# LED.net
KiCad netlist of a schematic drawn in Altium Designer
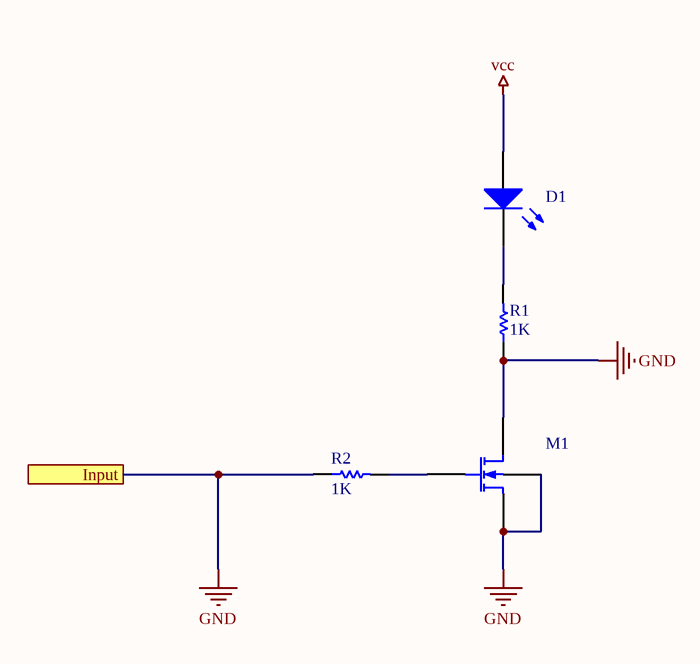
[diagram p0: LED.SchDoc]

(export (version "E")
  (design (tool "Eeschema 10.0.6"))
  (components
    (comp (ref "D1")
      (value "Light-Emitting Diode")
      (libsource (lib "Simulation Generic Components") (part "LED"))
    )
    (comp (ref "M1")
      (value "N-channel MOS1 MOSFET Shichman and Hodges Model")
      (libsource (lib "Simulation Generic Components") (part "MOSFET N-ch Lev1"))
    )
    (comp (ref "R1")
      (value "1K")
      (description "Resistor")
      (libsource (lib "Simulation Generic Components") (part "Resistor"))
    )
    (comp (ref "R2")
      (value "1K")
      (description "Resistor")
      (libsource (lib "Simulation Generic Components") (part "Resistor"))
    )
  )
  (nets
    (net (code "1") (name "GND") (class "Default")
      (node (ref "M1") (pin "1") (pinfunction "D_1") (pintype "passive"))
      (node (ref "M1") (pin "3") (pinfunction "S_3") (pintype "passive"))
      (node (ref "M1") (pin "4") (pinfunction "B_4") (pintype "passive"))
      (node (ref "R1") (pin "1") (pinfunction "1_1") (pintype "passive"))
      (node (ref "R2") (pin "1") (pinfunction "1_1") (pintype "passive"))
    )
    (net (code "2") (name "Net-(D1-K)") (class "Default")
      (node (ref "D1") (pin "2") (pinfunction "K_2") (pintype "passive"))
      (node (ref "R1") (pin "2") (pinfunction "2_2") (pintype "passive"))
    )
    (net (code "3") (name "Net-(M1-G)") (class "Default")
      (node (ref "M1") (pin "2") (pinfunction "G_2") (pintype "passive"))
      (node (ref "R2") (pin "2") (pinfunction "2_2") (pintype "passive"))
    )
    (net (code "4") (name "vcc") (class "Default")
      (node (ref "D1") (pin "1") (pinfunction "A_1") (pintype "passive"))
    )
  )
)
